# Sch.net
KiCad netlist of a schematic drawn in Altium Designer
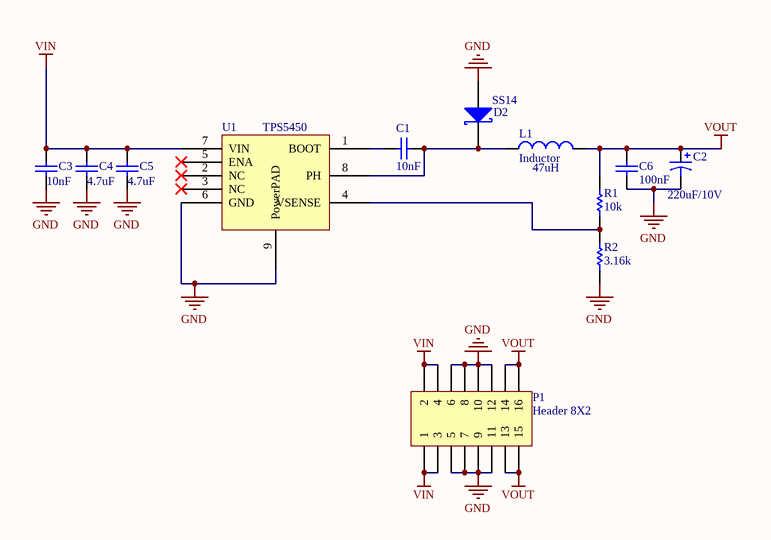
[diagram p0: Sch.SchDoc]

(export (version "E")
  (design (tool "Eeschema 10.0.6"))
  (components
    (comp (ref "C1")
      (value "10nF")
      (footprint "CAP1608(0603)")
      (description "Capacitor")
      (fields (field (name "PUBLISHER") "Altium Limited"))
      (libsource (lib "Miscellaneous Devices") (part "Cap"))
    )
    (comp (ref "C2")
      (value "220uF/10V")
      (footprint "CAP 5.0*10*12.5 - BK")
      (description "Polarized Capacitor (Radial)")
      (fields (field (name "PUBLISHER") "Altium Limited"))
      (libsource (lib "Miscellaneous Devices") (part "Cap Pol1"))
    )
    (comp (ref "C3")
      (value "10nF")
      (footprint "CAP1608(0603)")
      (description "Capacitor")
      (fields (field (name "PUBLISHER") "Altium Limited"))
      (libsource (lib "Miscellaneous Devices") (part "Cap"))
    )
    (comp (ref "C4")
      (value "4.7uF")
      (footprint "CAPC3216N")
      (description "Capacitor")
      (fields (field (name "PUBLISHER") "Altium Limited"))
      (libsource (lib "Miscellaneous Devices") (part "Cap"))
    )
    (comp (ref "C5")
      (value "4.7uF")
      (footprint "CAPC3216N")
      (description "Capacitor")
      (fields (field (name "PUBLISHER") "Altium Limited"))
      (libsource (lib "Miscellaneous Devices") (part "Cap"))
    )
    (comp (ref "C6")
      (value "100nF")
      (footprint "CAP1608(0603)")
      (description "Capacitor")
      (fields (field (name "PUBLISHER") "Altium Limited"))
      (libsource (lib "Miscellaneous Devices") (part "Cap"))
    )
    (comp (ref "D2")
      (value "SS14")
      (footprint "DIODE_SMA")
      (description "Schottky Diode")
      (fields (field (name "PUBLISHER") "Altium Limited"))
      (libsource (lib "Miscellaneous Devices") (part "D Schottky"))
    )
    (comp (ref "L1")
      (value "Inductor")
      (footprint "NR5012")
      (fields (field (name "ALTIUM_VALUE") "47uH") (field (name "PUBLISHER") "Altium Limited"))
      (libsource (lib "Miscellaneous Devices") (part "Inductor"))
    )
    (comp (ref "P1")
      (value "Header 8X2")
      (footprint "HDR2X8")
      (description "Header, 8-Pin, Dual row")
      (fields (field (name "PUBLISHER") "Altium Limited"))
      (libsource (lib "Miscellaneous Connectors") (part "Header 8X2"))
    )
    (comp (ref "R1")
      (value "10k")
      (footprint "RES1608(0603)")
      (description "Resistor")
      (fields (field (name "PUBLISHER") "Altium Limited"))
      (libsource (lib "Miscellaneous Devices") (part "Res1"))
    )
    (comp (ref "R2")
      (value "3.16k")
      (footprint "RES1608(0603)")
      (description "Resistor")
      (fields (field (name "PUBLISHER") "Altium Limited"))
      (libsource (lib "Miscellaneous Devices") (part "Res1"))
    )
    (comp (ref "U1") (value "TPS5450") (footprint "TPS5450") (libsource (lib "MySchlib") (part "TPS5450")))
  )
  (nets
    (net (code "1") (name "GND") (class "Default")
      (node (ref "C2") (pin "2") (pinfunction "2_2") (pintype "passive"))
      (node (ref "C3") (pin "2") (pinfunction "2_2") (pintype "passive"))
      (node (ref "C4") (pin "2") (pinfunction "2_2") (pintype "passive"))
      (node (ref "C5") (pin "2") (pinfunction "2_2") (pintype "passive"))
      (node (ref "C6") (pin "2") (pinfunction "2_2") (pintype "passive"))
      (node (ref "D2") (pin "1") (pinfunction "A_1") (pintype "passive"))
      (node (ref "P1") (pin "10") (pinfunction "10_10") (pintype "passive"))
      (node (ref "P1") (pin "11") (pinfunction "11_11") (pintype "passive"))
      (node (ref "P1") (pin "12") (pinfunction "12_12") (pintype "passive"))
      (node (ref "P1") (pin "5") (pinfunction "5_5") (pintype "passive"))
      (node (ref "P1") (pin "6") (pinfunction "6_6") (pintype "passive"))
      (node (ref "P1") (pin "7") (pinfunction "7_7") (pintype "passive"))
      (node (ref "P1") (pin "8") (pinfunction "8_8") (pintype "passive"))
      (node (ref "P1") (pin "9") (pinfunction "9_9") (pintype "passive"))
      (node (ref "R2") (pin "1") (pinfunction "1_1") (pintype "passive"))
      (node (ref "U1") (pin "6") (pinfunction "GND_6") (pintype "passive"))
      (node (ref "U1") (pin "9") (pinfunction "PowerPAD_9") (pintype "passive"))
    )
    (net (code "2") (name "Net-(D2-K)") (class "Default")
      (node (ref "C1") (pin "2") (pinfunction "2_2") (pintype "passive"))
      (node (ref "D2") (pin "2") (pinfunction "K_2") (pintype "passive"))
      (node (ref "L1") (pin "1") (pinfunction "1_1") (pintype "passive"))
      (node (ref "U1") (pin "8") (pinfunction "PH_8") (pintype "passive"))
    )
    (net (code "3") (name "Net-(U1-BOOT)") (class "Default")
      (node (ref "C1") (pin "1") (pinfunction "1_1") (pintype "passive"))
      (node (ref "U1") (pin "1") (pinfunction "BOOT_1") (pintype "passive"))
    )
    (net (code "4") (name "Net-(U1-VSENSE)") (class "Default")
      (node (ref "R1") (pin "1") (pinfunction "1_1") (pintype "passive"))
      (node (ref "R2") (pin "2") (pinfunction "2_2") (pintype "passive"))
      (node (ref "U1") (pin "4") (pinfunction "VSENSE_4") (pintype "passive"))
    )
    (net (code "5") (name "VIN") (class "Default")
      (node (ref "C3") (pin "1") (pinfunction "1_1") (pintype "passive"))
      (node (ref "C4") (pin "1") (pinfunction "1_1") (pintype "passive"))
      (node (ref "C5") (pin "1") (pinfunction "1_1") (pintype "passive"))
      (node (ref "P1") (pin "1") (pinfunction "1_1") (pintype "passive"))
      (node (ref "P1") (pin "2") (pinfunction "2_2") (pintype "passive"))
      (node (ref "P1") (pin "3") (pinfunction "3_3") (pintype "passive"))
      (node (ref "P1") (pin "4") (pinfunction "4_4") (pintype "passive"))
      (node (ref "U1") (pin "7") (pinfunction "VIN_7") (pintype "passive"))
    )
    (net (code "6") (name "VOUT") (class "Default")
      (node (ref "C2") (pin "1") (pinfunction "1_1") (pintype "passive"))
      (node (ref "C6") (pin "1") (pinfunction "1_1") (pintype "passive"))
      (node (ref "L1") (pin "2") (pinfunction "2_2") (pintype "passive"))
      (node (ref "P1") (pin "13") (pinfunction "13_13") (pintype "passive"))
      (node (ref "P1") (pin "14") (pinfunction "14_14") (pintype "passive"))
      (node (ref "P1") (pin "15") (pinfunction "15_15") (pintype "passive"))
      (node (ref "P1") (pin "16") (pinfunction "16_16") (pintype "passive"))
      (node (ref "R1") (pin "2") (pinfunction "2_2") (pintype "passive"))
    )
    (net (code "7") (name "unconnected-(U1-ENA-Pad5)") (class "Default")
      (node (ref "U1") (pin "5") (pinfunction "ENA_5") (pintype "passive+no_connect"))
    )
    (net (code "8") (name "unconnected-(U1-NC-Pad2)") (class "Default")
      (node (ref "U1") (pin "2") (pinfunction "NC_2") (pintype "passive+no_connect"))
    )
    (net (code "9") (name "unconnected-(U1-NC-Pad3)") (class "Default")
      (node (ref "U1") (pin "3") (pinfunction "NC_3") (pintype "passive+no_connect"))
    )
  )
)
